# ProDoc_24_4_6__2025-08-03.net
KiCad netlist of a schematic drawn in EasyEDA Pro
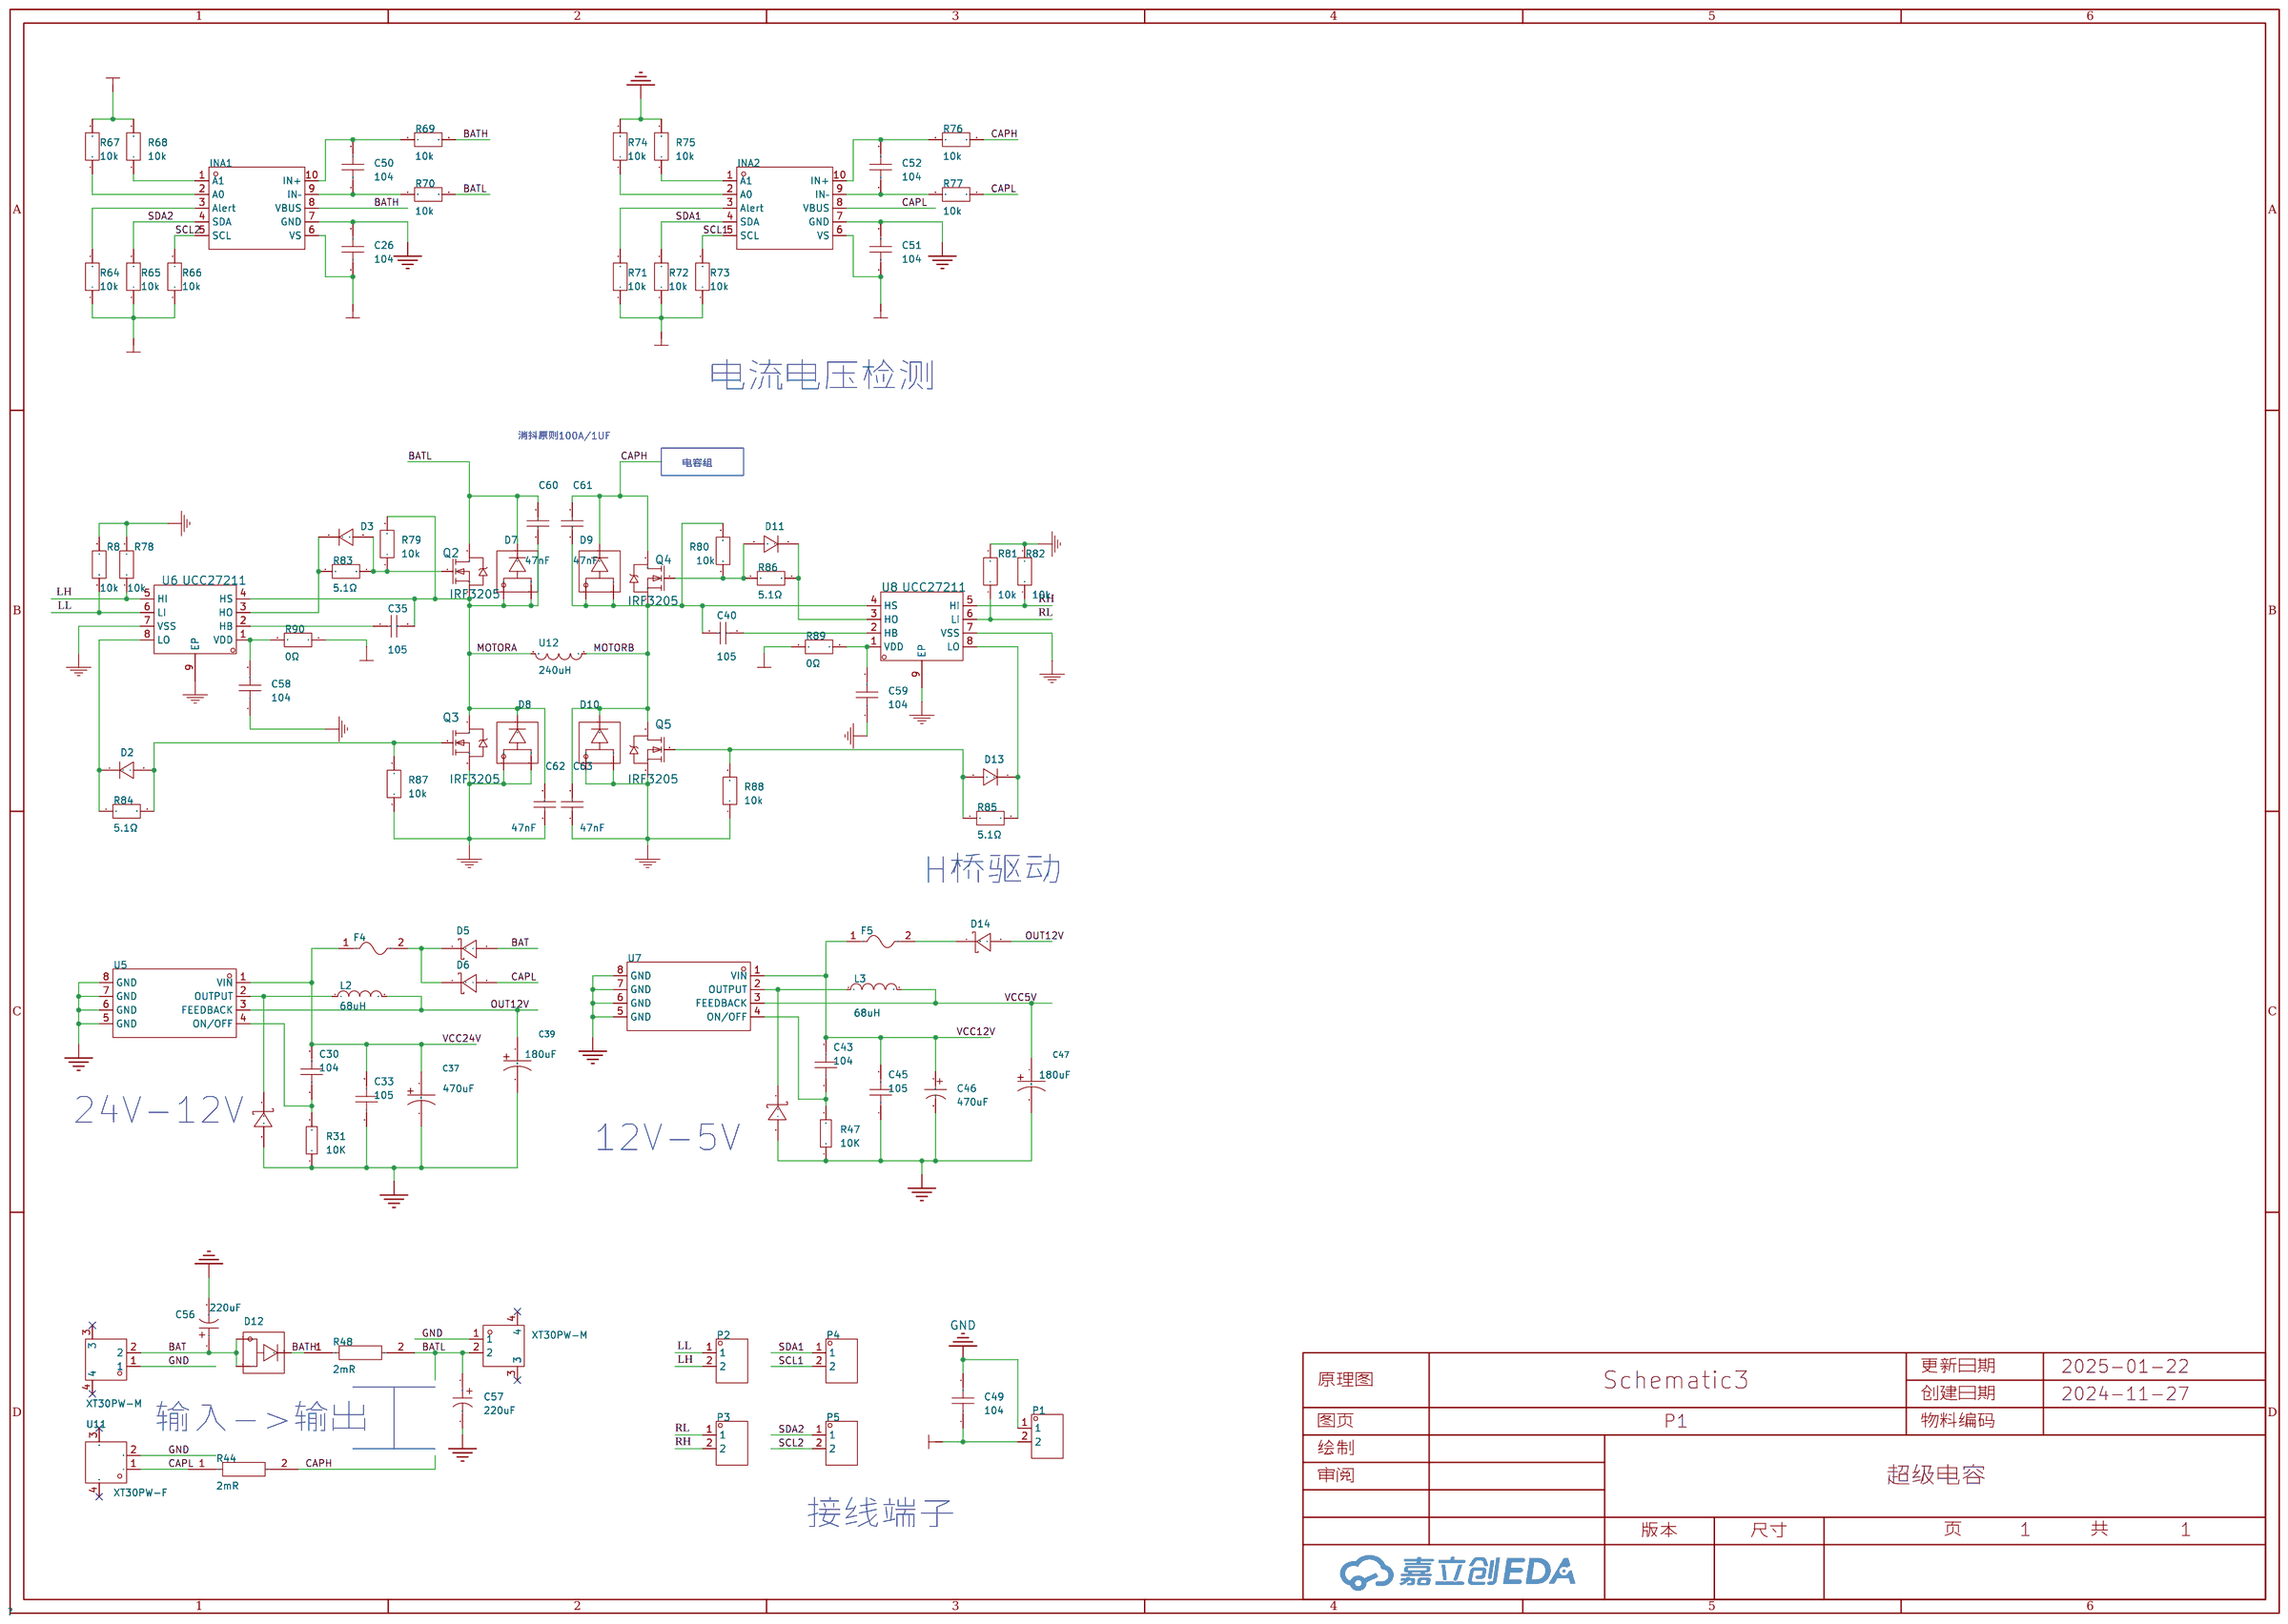
[diagram p0: schematic sheet]

(export (version "E")
  (design (tool "Eeschema 10.0.6"))
  (components
    (comp (ref "C26")
      (value "104")
      (footprint "easyedapro:C0603")
      (libsource (lib "easyedapro") (part "CapAcitance"))
    )
    (comp (ref "C30")
      (value "104")
      (footprint "easyedapro:C0603")
      (libsource (lib "easyedapro") (part "CapAcitance"))
    )
    (comp (ref "C33")
      (value "105")
      (footprint "easyedapro:C0603")
      (libsource (lib "easyedapro") (part "CapAcitance"))
    )
    (comp (ref "C35")
      (value "105")
      (footprint "easyedapro:C1206")
      (description "容值:10uF;精度:±10%;额定电压:50V;材质(温度系数):X5R;")
      (fields
        (field (name "Manufacturer Part") "CL31A106KBHNNNE")
        (field (name "Manufacturer") "SAMSUNG(三星)")
      )
      (libsource (lib "easyedapro") (part "CL31A106KBHNNNE"))
    )
    (comp (ref "C37")
      (value "470uF")
      (footprint "easyedapro:CAP-SMD_BD12.5-L13.0-W13.0-RD")
      (description "容值:470uF;精度:±20%;额定电压:50V;纹波电流:530mA@120Hz;等效串联电阻:-;")
      (fields (field (name "Manufacturer Part") "RVT1H471M1213") (field (name "Manufacturer") "ROQANG(容强)"))
      (libsource (lib "easyedapro") (part "RVT1H471M1213"))
    )
    (comp (ref "C39")
      (value "180uF")
      (footprint "easyedapro:CAP-SMD_BD8.0-L8.3-W8.3-FD")
      (fields (field (name "Manufacturer Part") "EEEFK1H181SP") (field (name "Manufacturer") "PANASONIC(松下)"))
      (libsource (lib "easyedapro") (part "EEEFK1H181SP"))
    )
    (comp (ref "C40")
      (value "105")
      (footprint "easyedapro:C1206")
      (description "容值:10uF;精度:±10%;额定电压:50V;材质(温度系数):X5R;")
      (fields
        (field (name "Manufacturer Part") "CL31A106KBHNNNE")
        (field (name "Manufacturer") "SAMSUNG(三星)")
      )
      (libsource (lib "easyedapro") (part "CL31A106KBHNNNE"))
    )
    (comp (ref "C43")
      (value "104")
      (footprint "easyedapro:C0603")
      (libsource (lib "easyedapro") (part "CapAcitance"))
    )
    (comp (ref "C45")
      (value "105")
      (footprint "easyedapro:C0603")
      (libsource (lib "easyedapro") (part "CapAcitance"))
    )
    (comp (ref "C46")
      (value "470uF")
      (footprint "easyedapro:CAP-SMD_BD10.0-L10.3-W10.3-FD")
      (description "容值:470uF;精度:±20%;额定电压:25V;纹波电流:286mA@120Hz;等效串联电阻:-;")
      (fields (field (name "Manufacturer Part") "RVT1E471M1010") (field (name "Manufacturer") "ROQANG(容强)"))
      (libsource (lib "easyedapro") (part "RVT1E471M1010"))
    )
    (comp (ref "C47")
      (value "180uF")
      (footprint "easyedapro:CAP-SMD_BD8.0-L8.3-W8.3-FD")
      (fields (field (name "Manufacturer Part") "EEEFK1H181SP") (field (name "Manufacturer") "PANASONIC(松下)"))
      (libsource (lib "easyedapro") (part "EEEFK1H181SP"))
    )
    (comp (ref "C49")
      (value "104")
      (footprint "easyedapro:C0603")
      (libsource (lib "easyedapro") (part "CapAcitance"))
    )
    (comp (ref "C50")
      (value "104")
      (footprint "easyedapro:C0603")
      (libsource (lib "easyedapro") (part "CapAcitance"))
    )
    (comp (ref "C51")
      (value "104")
      (footprint "easyedapro:C0603")
      (libsource (lib "easyedapro") (part "CapAcitance"))
    )
    (comp (ref "C52")
      (value "104")
      (footprint "easyedapro:C0603")
      (libsource (lib "easyedapro") (part "CapAcitance"))
    )
    (comp (ref "C56")
      (value "220uF")
      (footprint "easyedapro:CAP-SMD_BD6.3-L6.6-W6.6-FD")
      (description "容值:220uF;精度:±20%;额定电压:16V;纹波电流:110mA@120Hz;等效串联电阻:-;")
      (fields
        (field (name "Manufacturer Part") "RVT220UF16V67RV0015")
        (field (name "Manufacturer") "KNSCHA(科尼盛)")
      )
      (libsource (lib "easyedapro") (part "RVT220UF16V67RV0015"))
    )
    (comp (ref "C57")
      (value "220uF")
      (footprint "easyedapro:CAP-SMD_BD6.3-L6.6-W6.6-FD")
      (description "容值:220uF;精度:±20%;额定电压:16V;纹波电流:110mA@120Hz;等效串联电阻:-;")
      (fields
        (field (name "Manufacturer Part") "RVT220UF16V67RV0015")
        (field (name "Manufacturer") "KNSCHA(科尼盛)")
      )
      (libsource (lib "easyedapro") (part "RVT220UF16V67RV0015"))
    )
    (comp (ref "C58")
      (value "104")
      (footprint "easyedapro:C0603")
      (libsource (lib "easyedapro") (part "CapAcitance"))
    )
    (comp (ref "C59")
      (value "104")
      (footprint "easyedapro:C0603")
      (libsource (lib "easyedapro") (part "CapAcitance"))
    )
    (comp (ref "C60")
      (value "47nF")
      (footprint "easyedapro:C1206")
      (description "容值:10uF;精度:±10%;额定电压:50V;材质(温度系数):X5R;")
      (fields
        (field (name "Manufacturer Part") "CL31A106KBHNNNE")
        (field (name "Manufacturer") "SAMSUNG(三星)")
      )
      (libsource (lib "easyedapro") (part "CL31A106KBHNNNE"))
    )
    (comp (ref "C61")
      (value "47nF")
      (footprint "easyedapro:C1206")
      (description "容值:10uF;精度:±10%;额定电压:50V;材质(温度系数):X5R;")
      (fields
        (field (name "Manufacturer Part") "CL31A106KBHNNNE")
        (field (name "Manufacturer") "SAMSUNG(三星)")
      )
      (libsource (lib "easyedapro") (part "CL31A106KBHNNNE"))
    )
    (comp (ref "C62")
      (value "47nF")
      (footprint "easyedapro:C1206")
      (description "容值:10uF;精度:±10%;额定电压:50V;材质(温度系数):X5R;")
      (fields
        (field (name "Manufacturer Part") "CL31A106KBHNNNE")
        (field (name "Manufacturer") "SAMSUNG(三星)")
      )
      (libsource (lib "easyedapro") (part "CL31A106KBHNNNE"))
    )
    (comp (ref "C63")
      (value "47nF")
      (footprint "easyedapro:C1206")
      (description "容值:10uF;精度:±10%;额定电压:50V;材质(温度系数):X5R;")
      (fields
        (field (name "Manufacturer Part") "CL31A106KBHNNNE")
        (field (name "Manufacturer") "SAMSUNG(三星)")
      )
      (libsource (lib "easyedapro") (part "CL31A106KBHNNNE"))
    )
    (comp (ref "CN5")
      (value "XT30PW-M")
      (footprint "easyedapro:CONN-TH_XT30PW-M")
      (description "Socket,DCsupply,XT30,male,PIN:2")
      (fields (field (name "Manufacturer") "AMASS(艾迈斯)"))
      (libsource (lib "easyedapro") (part "XT30PW-M"))
    )
    (comp (ref "CN6")
      (value "XT30PW-M")
      (footprint "easyedapro:CONN-TH_XT30PW-M")
      (description "Socket,DCsupply,XT30,male,PIN:2")
      (fields (field (name "Manufacturer") "AMASS(艾迈斯)"))
      (libsource (lib "easyedapro") (part "XT30PW-M"))
    )
    (comp (ref "D2")
      (value "1N4148W")
      (footprint "easyedapro:SOD-123F_L2.7-W1.6-LS3.8-RD")
      (description "二极管配置:独立式;功率:400mW;直流反向耐压(Vr):75V;平均整流电流(Io):150mA;正向压降(Vf):1V@50mA;反向恢复时间(trr):4ns;")
      (fields (field (name "Manufacturer") "ST(先科)"))
      (libsource (lib "easyedapro") (part "1N4148W_C81598"))
    )
    (comp (ref "D3")
      (value "1N4148W")
      (footprint "easyedapro:SOD-123F_L2.7-W1.6-LS3.8-RD")
      (description "二极管配置:独立式;功率:400mW;直流反向耐压(Vr):75V;平均整流电流(Io):150mA;正向压降(Vf):1V@50mA;反向恢复时间(trr):4ns;")
      (fields (field (name "Manufacturer") "ST(先科)"))
      (libsource (lib "easyedapro") (part "1N4148W_C81598"))
    )
    (comp (ref "D5")
      (value "SS34K")
      (footprint "easyedapro:SMA_L4.3-W2.6-LS5.2-RD")
      (description "二极管配置:独立式;直流反向耐压(Vr):40V;平均整流电流(Io):3A;正向压降(Vf):550mV@3A;反向电流(Ir):500uA@40V;")
      (fields (field (name "Manufacturer") "TDD(台冠电子)"))
      (libsource (lib "easyedapro") (part "SS34K"))
    )
    (comp (ref "D6")
      (value "SS34K")
      (footprint "easyedapro:SMA_L4.3-W2.6-LS5.2-RD")
      (description "二极管配置:独立式;直流反向耐压(Vr):40V;平均整流电流(Io):3A;正向压降(Vf):550mV@3A;反向电流(Ir):500uA@40V;")
      (fields (field (name "Manufacturer") "TDD(台冠电子)"))
      (libsource (lib "easyedapro") (part "SS34K"))
    )
    (comp (ref "D7")
      (value "PSA2060LT")
      (footprint "easyedapro:PS-277A_L6.3-W4.7-LS7.1-RD")
      (description "直流反向耐压(Vr):60V;平均整流电流(Io):20A;正向压降(Vf):550mV@20A;")
      (fields (field (name "Manufacturer") "PINGWEI(平伟)"))
      (libsource (lib "easyedapro") (part "PSA2060LT"))
    )
    (comp (ref "D8")
      (value "PSA2060LT")
      (footprint "easyedapro:PS-277A_L6.3-W4.7-LS7.1-RD")
      (description "直流反向耐压(Vr):60V;平均整流电流(Io):20A;正向压降(Vf):550mV@20A;")
      (fields (field (name "Manufacturer") "PINGWEI(平伟)"))
      (libsource (lib "easyedapro") (part "PSA2060LT"))
    )
    (comp (ref "D9")
      (value "PSA2060LT")
      (footprint "easyedapro:PS-277A_L6.3-W4.7-LS7.1-RD")
      (description "直流反向耐压(Vr):60V;平均整流电流(Io):20A;正向压降(Vf):550mV@20A;")
      (fields (field (name "Manufacturer") "PINGWEI(平伟)"))
      (libsource (lib "easyedapro") (part "PSA2060LT"))
    )
    (comp (ref "D10")
      (value "PSA2060LT")
      (footprint "easyedapro:PS-277A_L6.3-W4.7-LS7.1-RD")
      (description "直流反向耐压(Vr):60V;平均整流电流(Io):20A;正向压降(Vf):550mV@20A;")
      (fields (field (name "Manufacturer") "PINGWEI(平伟)"))
      (libsource (lib "easyedapro") (part "PSA2060LT"))
    )
    (comp (ref "D11")
      (value "1N4148W")
      (footprint "easyedapro:SOD-123F_L2.7-W1.6-LS3.8-RD")
      (description "二极管配置:独立式;功率:400mW;直流反向耐压(Vr):75V;平均整流电流(Io):150mA;正向压降(Vf):1V@50mA;反向恢复时间(trr):4ns;")
      (fields (field (name "Manufacturer") "ST(先科)"))
      (libsource (lib "easyedapro") (part "1N4148W_C81598"))
    )
    (comp (ref "D12")
      (value "PSA2060LT")
      (footprint "easyedapro:PS-277A_L6.3-W4.7-LS7.1-RD")
      (description "直流反向耐压(Vr):60V;平均整流电流(Io):20A;正向压降(Vf):550mV@20A;")
      (fields (field (name "Manufacturer") "PINGWEI(平伟)"))
      (libsource (lib "easyedapro") (part "PSA2060LT"))
    )
    (comp (ref "D13")
      (value "1N4148W")
      (footprint "easyedapro:SOD-123F_L2.7-W1.6-LS3.8-RD")
      (description "二极管配置:独立式;功率:400mW;直流反向耐压(Vr):75V;平均整流电流(Io):150mA;正向压降(Vf):1V@50mA;反向恢复时间(trr):4ns;")
      (fields (field (name "Manufacturer") "ST(先科)"))
      (libsource (lib "easyedapro") (part "1N4148W_C81598"))
    )
    (comp (ref "D14")
      (value "SS34K")
      (footprint "easyedapro:SMA_L4.3-W2.6-LS5.2-RD")
      (description "二极管配置:独立式;直流反向耐压(Vr):40V;平均整流电流(Io):3A;正向压降(Vf):550mV@3A;反向电流(Ir):500uA@40V;")
      (fields (field (name "Manufacturer") "TDD(台冠电子)"))
      (libsource (lib "easyedapro") (part "SS34K"))
    )
    (comp (ref "F4")
      (value "nSMD020-30V")
      (footprint "easyedapro:F1206")
      (description "最大电压:30V;最大电流:100A;保持电流:200mA;跳闸电流:460mA;")
      (fields (field (name "Manufacturer") "台湾陆海"))
      (libsource (lib "easyedapro") (part "nSMD020-30V"))
    )
    (comp (ref "F5")
      (value "nSMD020-30V")
      (footprint "easyedapro:F1206")
      (description "最大电压:30V;最大电流:100A;保持电流:200mA;跳闸电流:460mA;")
      (fields (field (name "Manufacturer") "台湾陆海"))
      (libsource (lib "easyedapro") (part "nSMD020-30V"))
    )
    (comp (ref "INA1")
      (value "INA226AIDGST")
      (footprint "easyedapro:VSSOP-10_L3.0-W3.0-P0.50-LS4.9-BL")
      (fields (field (name "Manufacturer") "TI(德州仪器)"))
      (libsource (lib "easyedapro") (part "INA226AIDGST"))
    )
    (comp (ref "INA2")
      (value "INA226AIDGST")
      (footprint "easyedapro:VSSOP-10_L3.0-W3.0-P0.50-LS4.9-BL")
      (fields (field (name "Manufacturer") "TI(德州仪器)"))
      (libsource (lib "easyedapro") (part "INA226AIDGST"))
    )
    (comp (ref "L2")
      (value "68uH")
      (footprint "easyedapro:IND-SMD_L11.2-W10.0_GPSR1050")
      (description "类型:一体成型电感;电感值:68uH;精度:±20%;额定电流:-;饱和电流(Isat):-;")
      (fields (field (name "Manufacturer Part") "GPSR1050-680MS") (field (name "Manufacturer") "Gantong(感通)"))
      (libsource (lib "easyedapro") (part "GPSR1050-680MS"))
    )
    (comp (ref "L3")
      (value "68uH")
      (footprint "easyedapro:IND-SMD_L7.1-W6.6-1")
      (description "电感值:68uH;精度:±20%;额定电流:2A;饱和电流(Isat):2.5A;")
      (fields
        (field (name "Manufacturer Part") "PSPMAA0605H-680M-IGF")
        (field (name "Manufacturer") "PROD(谱罗德)")
      )
      (libsource (lib "easyedapro") (part "PSPMAA0605H-680M-IGF"))
    )
    (comp (ref "P1")
      (value "WJ15EDGRC-3.81-2P")
      (footprint "easyedapro:CONN-TH_2P-P3.81_WJ15EDGRC-3.81-2P")
      (description "连接器类型:板端/插座-闭口;间距:3.81mm;排数:1;每排PIN数:2;安装方式:弯针;颜色:绿色;")
      (fields (field (name "Manufacturer") "KANGNEX(康奈克斯电气)"))
      (libsource (lib "easyedapro") (part "WJ15EDGRC-3.81-2P"))
    )
    (comp (ref "P2")
      (value "WJ15EDGRC-3.81-2P")
      (footprint "easyedapro:CONN-TH_2P-P3.81_WJ15EDGRC-3.81-2P")
      (description "连接器类型:板端/插座-闭口;间距:3.81mm;排数:1;每排PIN数:2;安装方式:弯针;颜色:绿色;")
      (fields (field (name "Manufacturer") "KANGNEX(康奈克斯电气)"))
      (libsource (lib "easyedapro") (part "WJ15EDGRC-3.81-2P"))
    )
    (comp (ref "P3")
      (value "WJ15EDGRC-3.81-2P")
      (footprint "easyedapro:CONN-TH_2P-P3.81_WJ15EDGRC-3.81-2P")
      (description "连接器类型:板端/插座-闭口;间距:3.81mm;排数:1;每排PIN数:2;安装方式:弯针;颜色:绿色;")
      (fields (field (name "Manufacturer") "KANGNEX(康奈克斯电气)"))
      (libsource (lib "easyedapro") (part "WJ15EDGRC-3.81-2P"))
    )
    (comp (ref "P4")
      (value "WJ15EDGRC-3.81-2P")
      (footprint "easyedapro:CONN-TH_2P-P3.81_WJ15EDGRC-3.81-2P")
      (description "连接器类型:板端/插座-闭口;间距:3.81mm;排数:1;每排PIN数:2;安装方式:弯针;颜色:绿色;")
      (fields (field (name "Manufacturer") "KANGNEX(康奈克斯电气)"))
      (libsource (lib "easyedapro") (part "WJ15EDGRC-3.81-2P"))
    )
    (comp (ref "P5")
      (value "WJ15EDGRC-3.81-2P")
      (footprint "easyedapro:CONN-TH_2P-P3.81_WJ15EDGRC-3.81-2P")
      (description "连接器类型:板端/插座-闭口;间距:3.81mm;排数:1;每排PIN数:2;安装方式:弯针;颜色:绿色;")
      (fields (field (name "Manufacturer") "KANGNEX(康奈克斯电气)"))
      (libsource (lib "easyedapro") (part "WJ15EDGRC-3.81-2P"))
    )
    (comp (ref "Q2")
      (value "IRF3205")
      (footprint "easyedapro:TO-263-3_L10.2-W10.7-P5.08-LS16.2-BR")
      (fields
        (field (name "Manufacturer Part") "IRF3205ZSTRLPBF")
        (field (name "Manufacturer") "InfineonTechnologies")
      )
      (libsource (lib "easyedapro") (part "IRF3205ZSTRLPBF"))
    )
    (comp (ref "Q3")
      (value "IRF3205")
      (footprint "easyedapro:TO-263-3_L10.2-W10.7-P5.08-LS16.2-BR")
      (fields
        (field (name "Manufacturer Part") "IRF3205ZSTRLPBF")
        (field (name "Manufacturer") "InfineonTechnologies")
      )
      (libsource (lib "easyedapro") (part "IRF3205ZSTRLPBF"))
    )
    (comp (ref "Q4")
      (value "IRF3205")
      (footprint "easyedapro:TO-263-3_L10.2-W10.7-P5.08-LS16.2-BR")
      (fields
        (field (name "Manufacturer Part") "IRF3205ZSTRLPBF")
        (field (name "Manufacturer") "InfineonTechnologies")
      )
      (libsource (lib "easyedapro") (part "IRF3205ZSTRLPBF"))
    )
    (comp (ref "Q5")
      (value "IRF3205")
      (footprint "easyedapro:TO-263-3_L10.2-W10.7-P5.08-LS16.2-BR")
      (fields
        (field (name "Manufacturer Part") "IRF3205ZSTRLPBF")
        (field (name "Manufacturer") "InfineonTechnologies")
      )
      (libsource (lib "easyedapro") (part "IRF3205ZSTRLPBF"))
    )
    (comp (ref "R8")
      (value "10k")
      (footprint "easyedapro:R0603")
      (description "电阻类型:-;阻值:10kΩ;精度:±0.1%;功率:-;温度系数:±50ppm/;最大工作电压:50V;工作温度范围:-55~+125;")
      (fields (field (name "Manufacturer Part") "AR03BTD1002") (field (name "Manufacturer") "Viking(光颉)"))
      (libsource (lib "easyedapro") (part "AR03BTD1002"))
    )
    (comp (ref "R31") (value "10K") (footprint "easyedapro:R0603") (libsource (lib "easyedapro") (part "电阻")))
    (comp (ref "R44")
      (value "2mR")
      (footprint "easyedapro:RES-SMD_L6.4-W3.2-1")
      (description "电阻类型:采样电阻;阻值:30mΩ;精度:±1%;功率:2W;安装方式:贴片;")
      (fields
        (field (name "Manufacturer Part") "LCSR2512FR030Q9L")
        (field (name "Manufacturer") "RESI(开步睿思）")
      )
      (libsource (lib "easyedapro") (part "LCSR2512FR030Q9L"))
    )
    (comp (ref "R47") (value "10K") (footprint "easyedapro:R0603") (libsource (lib "easyedapro") (part "电阻")))
    (comp (ref "R48")
      (value "2mR")
      (footprint "easyedapro:RES-SMD_L6.4-W3.2-1")
      (description "电阻类型:采样电阻;阻值:30mΩ;精度:±1%;功率:2W;安装方式:贴片;")
      (fields
        (field (name "Manufacturer Part") "LCSR2512FR030Q9L")
        (field (name "Manufacturer") "RESI(开步睿思）")
      )
      (libsource (lib "easyedapro") (part "LCSR2512FR030Q9L"))
    )
    (comp (ref "R64")
      (value "10k")
      (footprint "easyedapro:R0603")
      (description "电阻类型:-;阻值:10kΩ;精度:±0.1%;功率:-;温度系数:±50ppm/;最大工作电压:50V;工作温度范围:-55~+125;")
      (fields (field (name "Manufacturer Part") "AR03BTD1002") (field (name "Manufacturer") "Viking(光颉)"))
      (libsource (lib "easyedapro") (part "AR03BTD1002"))
    )
    (comp (ref "R65")
      (value "10k")
      (footprint "easyedapro:R0603")
      (description "电阻类型:-;阻值:10kΩ;精度:±0.1%;功率:-;温度系数:±50ppm/;最大工作电压:50V;工作温度范围:-55~+125;")
      (fields (field (name "Manufacturer Part") "AR03BTD1002") (field (name "Manufacturer") "Viking(光颉)"))
      (libsource (lib "easyedapro") (part "AR03BTD1002"))
    )
    (comp (ref "R66")
      (value "10k")
      (footprint "easyedapro:R0603")
      (description "电阻类型:-;阻值:10kΩ;精度:±0.1%;功率:-;温度系数:±50ppm/;最大工作电压:50V;工作温度范围:-55~+125;")
      (fields (field (name "Manufacturer Part") "AR03BTD1002") (field (name "Manufacturer") "Viking(光颉)"))
      (libsource (lib "easyedapro") (part "AR03BTD1002"))
    )
    (comp (ref "R67")
      (value "10k")
      (footprint "easyedapro:R0603")
      (description "电阻类型:-;阻值:10kΩ;精度:±0.1%;功率:-;温度系数:±50ppm/;最大工作电压:50V;工作温度范围:-55~+125;")
      (fields (field (name "Manufacturer Part") "AR03BTD1002") (field (name "Manufacturer") "Viking(光颉)"))
      (libsource (lib "easyedapro") (part "AR03BTD1002"))
    )
    (comp (ref "R68")
      (value "10k")
      (footprint "easyedapro:R0603")
      (description "电阻类型:-;阻值:10kΩ;精度:±0.1%;功率:-;温度系数:±50ppm/;最大工作电压:50V;工作温度范围:-55~+125;")
      (fields (field (name "Manufacturer Part") "AR03BTD1002") (field (name "Manufacturer") "Viking(光颉)"))
      (libsource (lib "easyedapro") (part "AR03BTD1002"))
    )
    (comp (ref "R69")
      (value "10k")
      (footprint "easyedapro:R0603")
      (description "电阻类型:-;阻值:10kΩ;精度:±0.1%;功率:-;温度系数:±50ppm/;最大工作电压:50V;工作温度范围:-55~+125;")
      (fields (field (name "Manufacturer Part") "AR03BTD1002") (field (name "Manufacturer") "Viking(光颉)"))
      (libsource (lib "easyedapro") (part "AR03BTD1002"))
    )
    (comp (ref "R70")
      (value "10k")
      (footprint "easyedapro:R0603")
      (description "电阻类型:-;阻值:10kΩ;精度:±0.1%;功率:-;温度系数:±50ppm/;最大工作电压:50V;工作温度范围:-55~+125;")
      (fields (field (name "Manufacturer Part") "AR03BTD1002") (field (name "Manufacturer") "Viking(光颉)"))
      (libsource (lib "easyedapro") (part "AR03BTD1002"))
    )
    (comp (ref "R71")
      (value "10k")
      (footprint "easyedapro:R0603")
      (description "电阻类型:-;阻值:10kΩ;精度:±0.1%;功率:-;温度系数:±50ppm/;最大工作电压:50V;工作温度范围:-55~+125;")
      (fields (field (name "Manufacturer Part") "AR03BTD1002") (field (name "Manufacturer") "Viking(光颉)"))
      (libsource (lib "easyedapro") (part "AR03BTD1002"))
    )
    (comp (ref "R72")
      (value "10k")
      (footprint "easyedapro:R0603")
      (description "电阻类型:-;阻值:10kΩ;精度:±0.1%;功率:-;温度系数:±50ppm/;最大工作电压:50V;工作温度范围:-55~+125;")
      (fields (field (name "Manufacturer Part") "AR03BTD1002") (field (name "Manufacturer") "Viking(光颉)"))
      (libsource (lib "easyedapro") (part "AR03BTD1002"))
    )
    (comp (ref "R73")
      (value "10k")
      (footprint "easyedapro:R0603")
      (description "电阻类型:-;阻值:10kΩ;精度:±0.1%;功率:-;温度系数:±50ppm/;最大工作电压:50V;工作温度范围:-55~+125;")
      (fields (field (name "Manufacturer Part") "AR03BTD1002") (field (name "Manufacturer") "Viking(光颉)"))
      (libsource (lib "easyedapro") (part "AR03BTD1002"))
    )
    (comp (ref "R74")
      (value "10k")
      (footprint "easyedapro:R0603")
      (description "电阻类型:-;阻值:10kΩ;精度:±0.1%;功率:-;温度系数:±50ppm/;最大工作电压:50V;工作温度范围:-55~+125;")
      (fields (field (name "Manufacturer Part") "AR03BTD1002") (field (name "Manufacturer") "Viking(光颉)"))
      (libsource (lib "easyedapro") (part "AR03BTD1002"))
    )
    (comp (ref "R75")
      (value "10k")
      (footprint "easyedapro:R0603")
      (description "电阻类型:-;阻值:10kΩ;精度:±0.1%;功率:-;温度系数:±50ppm/;最大工作电压:50V;工作温度范围:-55~+125;")
      (fields (field (name "Manufacturer Part") "AR03BTD1002") (field (name "Manufacturer") "Viking(光颉)"))
      (libsource (lib "easyedapro") (part "AR03BTD1002"))
    )
    (comp (ref "R76")
      (value "10k")
      (footprint "easyedapro:R0603")
      (description "电阻类型:-;阻值:10kΩ;精度:±0.1%;功率:-;温度系数:±50ppm/;最大工作电压:50V;工作温度范围:-55~+125;")
      (fields (field (name "Manufacturer Part") "AR03BTD1002") (field (name "Manufacturer") "Viking(光颉)"))
      (libsource (lib "easyedapro") (part "AR03BTD1002"))
    )
    (comp (ref "R77")
      (value "10k")
      (footprint "easyedapro:R0603")
      (description "电阻类型:-;阻值:10kΩ;精度:±0.1%;功率:-;温度系数:±50ppm/;最大工作电压:50V;工作温度范围:-55~+125;")
      (fields (field (name "Manufacturer Part") "AR03BTD1002") (field (name "Manufacturer") "Viking(光颉)"))
      (libsource (lib "easyedapro") (part "AR03BTD1002"))
    )
    (comp (ref "R78")
      (value "10k")
      (footprint "easyedapro:R0603")
      (description "电阻类型:-;阻值:10kΩ;精度:±0.1%;功率:-;温度系数:±50ppm/;最大工作电压:50V;工作温度范围:-55~+125;")
      (fields (field (name "Manufacturer Part") "AR03BTD1002") (field (name "Manufacturer") "Viking(光颉)"))
      (libsource (lib "easyedapro") (part "AR03BTD1002"))
    )
    (comp (ref "R79")
      (value "10k")
      (footprint "easyedapro:R0603")
      (description "电阻类型:-;阻值:10kΩ;精度:±0.1%;功率:-;温度系数:±50ppm/;最大工作电压:50V;工作温度范围:-55~+125;")
      (fields (field (name "Manufacturer Part") "AR03BTD1002") (field (name "Manufacturer") "Viking(光颉)"))
      (libsource (lib "easyedapro") (part "AR03BTD1002"))
    )
    (comp (ref "R80")
      (value "10k")
      (footprint "easyedapro:R0603")
      (description "电阻类型:-;阻值:10kΩ;精度:±0.1%;功率:-;温度系数:±50ppm/;最大工作电压:50V;工作温度范围:-55~+125;")
      (fields (field (name "Manufacturer Part") "AR03BTD1002") (field (name "Manufacturer") "Viking(光颉)"))
      (libsource (lib "easyedapro") (part "AR03BTD1002"))
    )
    (comp (ref "R81")
      (value "10k")
      (footprint "easyedapro:R0603")
      (description "电阻类型:-;阻值:10kΩ;精度:±0.1%;功率:-;温度系数:±50ppm/;最大工作电压:50V;工作温度范围:-55~+125;")
      (fields (field (name "Manufacturer Part") "AR03BTD1002") (field (name "Manufacturer") "Viking(光颉)"))
      (libsource (lib "easyedapro") (part "AR03BTD1002"))
    )
    (comp (ref "R82")
      (value "10k")
      (footprint "easyedapro:R0603")
      (description "电阻类型:-;阻值:10kΩ;精度:±0.1%;功率:-;温度系数:±50ppm/;最大工作电压:50V;工作温度范围:-55~+125;")
      (fields (field (name "Manufacturer Part") "AR03BTD1002") (field (name "Manufacturer") "Viking(光颉)"))
      (libsource (lib "easyedapro") (part "AR03BTD1002"))
    )
    (comp (ref "R83")
      (value "5.1Ω")
      (footprint "easyedapro:R0603")
      (description "电阻类型:-;阻值:10kΩ;精度:±0.1%;功率:-;温度系数:±50ppm/;最大工作电压:50V;工作温度范围:-55~+125;")
      (fields (field (name "Manufacturer Part") "AR03BTD1002") (field (name "Manufacturer") "Viking(光颉)"))
      (libsource (lib "easyedapro") (part "AR03BTD1002"))
    )
    (comp (ref "R84")
      (value "5.1Ω")
      (footprint "easyedapro:R0603")
      (description "电阻类型:-;阻值:10kΩ;精度:±0.1%;功率:-;温度系数:±50ppm/;最大工作电压:50V;工作温度范围:-55~+125;")
      (fields (field (name "Manufacturer Part") "AR03BTD1002") (field (name "Manufacturer") "Viking(光颉)"))
      (libsource (lib "easyedapro") (part "AR03BTD1002"))
    )
    (comp (ref "R85")
      (value "5.1Ω")
      (footprint "easyedapro:R0603")
      (description "电阻类型:-;阻值:10kΩ;精度:±0.1%;功率:-;温度系数:±50ppm/;最大工作电压:50V;工作温度范围:-55~+125;")
      (fields (field (name "Manufacturer Part") "AR03BTD1002") (field (name "Manufacturer") "Viking(光颉)"))
      (libsource (lib "easyedapro") (part "AR03BTD1002"))
    )
    (comp (ref "R86")
      (value "5.1Ω")
      (footprint "easyedapro:R0603")
      (description "电阻类型:-;阻值:10kΩ;精度:±0.1%;功率:-;温度系数:±50ppm/;最大工作电压:50V;工作温度范围:-55~+125;")
      (fields (field (name "Manufacturer Part") "AR03BTD1002") (field (name "Manufacturer") "Viking(光颉)"))
      (libsource (lib "easyedapro") (part "AR03BTD1002"))
    )
    (comp (ref "R87")
      (value "10k")
      (footprint "easyedapro:R0603")
      (description "电阻类型:-;阻值:10kΩ;精度:±0.1%;功率:-;温度系数:±50ppm/;最大工作电压:50V;工作温度范围:-55~+125;")
      (fields (field (name "Manufacturer Part") "AR03BTD1002") (field (name "Manufacturer") "Viking(光颉)"))
      (libsource (lib "easyedapro") (part "AR03BTD1002"))
    )
    (comp (ref "R88")
      (value "10k")
      (footprint "easyedapro:R0603")
      (description "电阻类型:-;阻值:10kΩ;精度:±0.1%;功率:-;温度系数:±50ppm/;最大工作电压:50V;工作温度范围:-55~+125;")
      (fields (field (name "Manufacturer Part") "AR03BTD1002") (field (name "Manufacturer") "Viking(光颉)"))
      (libsource (lib "easyedapro") (part "AR03BTD1002"))
    )
    (comp (ref "R89")
      (value "0Ω")
      (footprint "easyedapro:R0603")
      (description "电阻类型:-;阻值:10kΩ;精度:±0.1%;功率:-;温度系数:±50ppm/;最大工作电压:50V;工作温度范围:-55~+125;")
      (fields (field (name "Manufacturer Part") "AR03BTD1002") (field (name "Manufacturer") "Viking(光颉)"))
      (libsource (lib "easyedapro") (part "AR03BTD1002"))
    )
    (comp (ref "R90")
      (value "0Ω")
      (footprint "easyedapro:R0603")
      (description "电阻类型:-;阻值:10kΩ;精度:±0.1%;功率:-;温度系数:±50ppm/;最大工作电压:50V;工作温度范围:-55~+125;")
      (fields (field (name "Manufacturer Part") "AR03BTD1002") (field (name "Manufacturer") "Viking(光颉)"))
      (libsource (lib "easyedapro") (part "AR03BTD1002"))
    )
    (comp (ref "SS2")
      (value "SS34K")
      (footprint "easyedapro:SMA_L4.3-W2.6-LS5.2-RD")
      (description "二极管配置:独立式;直流反向耐压(Vr):40V;平均整流电流(Io):3A;正向压降(Vf):550mV@3A;反向电流(Ir):500uA@40V;")
      (fields (field (name "Manufacturer") "TDD(台冠电子)"))
      (libsource (lib "easyedapro") (part "SS34K"))
    )
    (comp (ref "SS3")
      (value "SS34K")
      (footprint "easyedapro:SMA_L4.3-W2.6-LS5.2-RD")
      (description "二极管配置:独立式;直流反向耐压(Vr):40V;平均整流电流(Io):3A;正向压降(Vf):550mV@3A;反向电流(Ir):500uA@40V;")
      (fields (field (name "Manufacturer") "TDD(台冠电子)"))
      (libsource (lib "easyedapro") (part "SS34K"))
    )
    (comp (ref "U5")
      (value "XL1509-12")
      (footprint "easyedapro:SOIC-8_L4.9-W3.9-P1.27-LS6.0-BL")
      (fields (field (name "Manufacturer") "UMW(广东友台半导体)"))
      (libsource (lib "easyedapro") (part "XL1509-12"))
    )
    (comp (ref "U6")
      (value "UCC27211")
      (footprint "easyedapro:SOIC-8_L4.9-W3.9-P1.27-LS6.0-BL-EP")
      (fields
        (field (name "Manufacturer Part") "UCC27211DDAR")
        (field (name "Manufacturer") "TexasInstruments")
      )
      (libsource (lib "easyedapro") (part "UCC27211"))
    )
    (comp (ref "U7")
      (value "XL1509-12")
      (footprint "easyedapro:SOIC-8_L4.9-W3.9-P1.27-LS6.0-BL")
      (fields (field (name "Manufacturer") "UMW(广东友台半导体)"))
      (libsource (lib "easyedapro") (part "XL1509-12"))
    )
    (comp (ref "U8")
      (value "UCC27211")
      (footprint "easyedapro:SOIC-8_L4.9-W3.9-P1.27-LS6.0-BL-EP")
      (fields
        (field (name "Manufacturer Part") "UCC27211DDAR")
        (field (name "Manufacturer") "TexasInstruments")
      )
      (libsource (lib "easyedapro") (part "UCC27211"))
    )
    (comp (ref "U11")
      (value "XT30PW-F")
      (footprint "easyedapro:CONN-TH_XT30PW-F")
      (description "类别:-;类型1:-;")
      (fields (field (name "Manufacturer") "AMASS(艾迈斯)"))
      (libsource (lib "easyedapro") (part "XT30PW-F"))
    )
    (comp (ref "U12")
      (value "240uH")
      (footprint "easyedapro:IND-TH_L10.0-W6.0-P6.00")
      (description "电感值:60uH;精度:±10%;额定电流:-;饱和电流(Isat):-;类型:-;Q值:-;")
      (fields (field (name "Manufacturer Part") "DDGH00000050") (field (name "Manufacturer") "增益"))
      (libsource (lib "easyedapro") (part "DDGH00000050"))
    )
  )
  (nets
    (net (code "1") (name "/BAT") (class "Default")
      (node (ref "C56") (pin "1") (pinfunction "1_1") (pintype "input"))
      (node (ref "CN5") (pin "2") (pinfunction "2_2") (pintype "input"))
      (node (ref "D12") (pin "1") (pinfunction "1_1") (pintype "input"))
      (node (ref "D12") (pin "2") (pinfunction "2_2") (pintype "input"))
      (node (ref "D5") (pin "2") (pinfunction "A_2") (pintype "input"))
    )
    (net (code "2") (name "/BATH") (class "Default")
      (node (ref "D12") (pin "3") (pinfunction "3_3") (pintype "input"))
      (node (ref "INA1") (pin "8") (pinfunction "VBUS_8") (pintype "input"))
      (node (ref "R48") (pin "1") (pinfunction "1_1") (pintype "input"))
      (node (ref "R69") (pin "2") (pinfunction "2_2") (pintype "input"))
    )
    (net (code "3") (name "/BATL") (class "Default")
      (node (ref "C57") (pin "1") (pinfunction "1_1") (pintype "input"))
      (node (ref "C60") (pin "2") (pinfunction "2_2") (pintype "input"))
      (node (ref "CN6") (pin "2") (pinfunction "2_2") (pintype "input"))
      (node (ref "D7") (pin "3") (pinfunction "3_3") (pintype "input"))
      (node (ref "Q2") (pin "2") (pinfunction "D_2") (pintype "input"))
      (node (ref "R48") (pin "2") (pinfunction "2_2") (pintype "input"))
      (node (ref "R70") (pin "1") (pinfunction "1_1") (pintype "input"))
    )
    (net (code "4") (name "/CAPH") (class "Default")
      (node (ref "C61") (pin "2") (pinfunction "2_2") (pintype "input"))
      (node (ref "D9") (pin "3") (pinfunction "3_3") (pintype "input"))
      (node (ref "Q4") (pin "2") (pinfunction "D_2") (pintype "input"))
      (node (ref "R44") (pin "2") (pinfunction "2_2") (pintype "input"))
      (node (ref "R76") (pin "1") (pinfunction "1_1") (pintype "input"))
    )
    (net (code "5") (name "/CAPL") (class "Default")
      (node (ref "D6") (pin "2") (pinfunction "A_2") (pintype "input"))
      (node (ref "INA2") (pin "8") (pinfunction "VBUS_8") (pintype "input"))
      (node (ref "R44") (pin "1") (pinfunction "1_1") (pintype "input"))
      (node (ref "R77") (pin "1") (pinfunction "1_1") (pintype "input"))
      (node (ref "U11") (pin "1") (pinfunction "1_1") (pintype "unspecified"))
    )
    (net (code "6") (name "/LH") (class "Default")
      (node (ref "P2") (pin "2") (pinfunction "2_2") (pintype "input"))
      (node (ref "R78") (pin "1") (pinfunction "1_1") (pintype "input"))
      (node (ref "U6") (pin "5") (pinfunction "HI_5") (pintype "input"))
    )
    (net (code "7") (name "/LL") (class "Default")
      (node (ref "P2") (pin "1") (pinfunction "1_1") (pintype "input"))
      (node (ref "R8") (pin "1") (pinfunction "1_1") (pintype "input"))
      (node (ref "U6") (pin "6") (pinfunction "LI_6") (pintype "input"))
    )
    (net (code "8") (name "/MOTORA") (class "Default")
      (node (ref "C35") (pin "2") (pinfunction "2_2") (pintype "input"))
      (node (ref "C60") (pin "1") (pinfunction "1_1") (pintype "input"))
      (node (ref "C62") (pin "2") (pinfunction "2_2") (pintype "input"))
      (node (ref "D7") (pin "1") (pinfunction "1_1") (pintype "input"))
      (node (ref "D7") (pin "2") (pinfunction "2_2") (pintype "input"))
      (node (ref "D8") (pin "3") (pinfunction "3_3") (pintype "input"))
      (node (ref "Q2") (pin "3") (pinfunction "S_3") (pintype "input"))
      (node (ref "Q3") (pin "2") (pinfunction "D_2") (pintype "input"))
      (node (ref "R79") (pin "2") (pinfunction "2_2") (pintype "input"))
      (node (ref "U12") (pin "2") (pinfunction "2_2") (pintype "unspecified"))
      (node (ref "U6") (pin "4") (pinfunction "HS_4") (pintype "input"))
    )
    (net (code "9") (name "/MOTORB") (class "Default")
      (node (ref "C40") (pin "1") (pinfunction "1_1") (pintype "input"))
      (node (ref "C61") (pin "1") (pinfunction "1_1") (pintype "input"))
      (node (ref "C63") (pin "2") (pinfunction "2_2") (pintype "input"))
      (node (ref "D10") (pin "3") (pinfunction "3_3") (pintype "input"))
      (node (ref "D9") (pin "1") (pinfunction "1_1") (pintype "input"))
      (node (ref "D9") (pin "2") (pinfunction "2_2") (pintype "input"))
      (node (ref "Q4") (pin "3") (pinfunction "S_3") (pintype "input"))
      (node (ref "Q5") (pin "2") (pinfunction "D_2") (pintype "input"))
      (node (ref "R80") (pin "2") (pinfunction "2_2") (pintype "input"))
      (node (ref "U12") (pin "1") (pinfunction "1_1") (pintype "unspecified"))
      (node (ref "U8") (pin "4") (pinfunction "HS_4") (pintype "input"))
    )
    (net (code "10") (name "/OUT12V") (class "Default")
      (node (ref "C39") (pin "1") (pinfunction "1_1") (pintype "input"))
      (node (ref "D14") (pin "2") (pinfunction "A_2") (pintype "input"))
      (node (ref "L2") (pin "2") (pinfunction "2_2") (pintype "input"))
      (node (ref "U5") (pin "3") (pinfunction "FEEDBACK_3") (pintype "input"))
    )
    (net (code "11") (name "/RH") (class "Default")
      (node (ref "P3") (pin "2") (pinfunction "2_2") (pintype "input"))
      (node (ref "R82") (pin "1") (pinfunction "1_1") (pintype "input"))
      (node (ref "U8") (pin "5") (pinfunction "HI_5") (pintype "input"))
    )
    (net (code "12") (name "/RL") (class "Default")
      (node (ref "P3") (pin "1") (pinfunction "1_1") (pintype "input"))
      (node (ref "R81") (pin "1") (pinfunction "1_1") (pintype "input"))
      (node (ref "U8") (pin "6") (pinfunction "LI_6") (pintype "input"))
    )
    (net (code "13") (name "/SCL1") (class "Default")
      (node (ref "INA2") (pin "5") (pinfunction "SCL_5") (pintype "input"))
      (node (ref "P4") (pin "2") (pinfunction "2_2") (pintype "input"))
      (node (ref "R73") (pin "2") (pinfunction "2_2") (pintype "input"))
    )
    (net (code "14") (name "/SCL2") (class "Default")
      (node (ref "INA1") (pin "5") (pinfunction "SCL_5") (pintype "input"))
      (node (ref "P5") (pin "2") (pinfunction "2_2") (pintype "input"))
      (node (ref "R66") (pin "2") (pinfunction "2_2") (pintype "input"))
    )
    (net (code "15") (name "/SDA1") (class "Default")
      (node (ref "INA2") (pin "4") (pinfunction "SDA_4") (pintype "input"))
      (node (ref "P4") (pin "1") (pinfunction "1_1") (pintype "input"))
      (node (ref "R72") (pin "2") (pinfunction "2_2") (pintype "input"))
    )
    (net (code "16") (name "/SDA2") (class "Default")
      (node (ref "INA1") (pin "4") (pinfunction "SDA_4") (pintype "input"))
      (node (ref "P5") (pin "1") (pinfunction "1_1") (pintype "input"))
      (node (ref "R65") (pin "2") (pinfunction "2_2") (pintype "input"))
    )
    (net (code "17") (name "/VCC24V") (class "Default")
      (node (ref "C30") (pin "2") (pinfunction "2_2") (pintype "input"))
      (node (ref "C33") (pin "2") (pinfunction "2_2") (pintype "input"))
      (node (ref "C37") (pin "1") (pinfunction "1_1") (pintype "input"))
      (node (ref "F4") (pin "1") (pinfunction "1_1") (pintype "unspecified"))
      (node (ref "U5") (pin "1") (pinfunction "VIN_1") (pintype "input"))
    )
    (net (code "18") (name "GND") (class "Default")
      (node (ref "C26") (pin "2") (pinfunction "2_2") (pintype "input"))
      (node (ref "C33") (pin "1") (pinfunction "1_1") (pintype "input"))
      (node (ref "C37") (pin "2") (pinfunction "2_2") (pintype "input"))
      (node (ref "C39") (pin "2") (pinfunction "2_2") (pintype "input"))
      (node (ref "C45") (pin "1") (pinfunction "1_1") (pintype "input"))
      (node (ref "C46") (pin "2") (pinfunction "2_2") (pintype "input"))
      (node (ref "C47") (pin "2") (pinfunction "2_2") (pintype "input"))
      (node (ref "C49") (pin "2") (pinfunction "2_2") (pintype "input"))
      (node (ref "C51") (pin "2") (pinfunction "2_2") (pintype "input"))
      (node (ref "C56") (pin "2") (pinfunction "2_2") (pintype "input"))
      (node (ref "C57") (pin "2") (pinfunction "2_2") (pintype "input"))
      (node (ref "C58") (pin "1") (pinfunction "1_1") (pintype "input"))
      (node (ref "C59") (pin "1") (pinfunction "1_1") (pintype "input"))
      (node (ref "C62") (pin "1") (pinfunction "1_1") (pintype "input"))
      (node (ref "C63") (pin "1") (pinfunction "1_1") (pintype "input"))
      (node (ref "CN5") (pin "1") (pinfunction "1_1") (pintype "input"))
      (node (ref "CN6") (pin "1") (pinfunction "1_1") (pintype "input"))
      (node (ref "D10") (pin "1") (pinfunction "1_1") (pintype "input"))
      (node (ref "D10") (pin "2") (pinfunction "2_2") (pintype "input"))
      (node (ref "D8") (pin "1") (pinfunction "1_1") (pintype "input"))
      (node (ref "D8") (pin "2") (pinfunction "2_2") (pintype "input"))
      (node (ref "INA1") (pin "7") (pinfunction "GND_7") (pintype "input"))
      (node (ref "INA2") (pin "7") (pinfunction "GND_7") (pintype "input"))
      (node (ref "P1") (pin "1") (pinfunction "1_1") (pintype "input"))
      (node (ref "Q3") (pin "3") (pinfunction "S_3") (pintype "input"))
      (node (ref "Q5") (pin "3") (pinfunction "S_3") (pintype "input"))
      (node (ref "R31") (pin "1") (pinfunction "1_1") (pintype "input"))
      (node (ref "R47") (pin "1") (pinfunction "1_1") (pintype "input"))
      (node (ref "R74") (pin "2") (pinfunction "2_2") (pintype "input"))
      (node (ref "R75") (pin "2") (pinfunction "2_2") (pintype "input"))
      (node (ref "R78") (pin "2") (pinfunction "2_2") (pintype "input"))
      (node (ref "R8") (pin "2") (pinfunction "2_2") (pintype "input"))
      (node (ref "R81") (pin "2") (pinfunction "2_2") (pintype "input"))
      (node (ref "R82") (pin "2") (pinfunction "2_2") (pintype "input"))
      (node (ref "R87") (pin "1") (pinfunction "1_1") (pintype "input"))
      (node (ref "R88") (pin "1") (pinfunction "1_1") (pintype "input"))
      (node (ref "SS2") (pin "2") (pinfunction "A_2") (pintype "input"))
      (node (ref "SS3") (pin "2") (pinfunction "A_2") (pintype "input"))
      (node (ref "U11") (pin "2") (pinfunction "2_2") (pintype "unspecified"))
      (node (ref "U5") (pin "5") (pinfunction "GND_5") (pintype "input"))
      (node (ref "U5") (pin "6") (pinfunction "GND_6") (pintype "input"))
      (node (ref "U5") (pin "7") (pinfunction "GND_7") (pintype "input"))
      (node (ref "U5") (pin "8") (pinfunction "GND_8") (pintype "input"))
      (node (ref "U6") (pin "7") (pinfunction "VSS_7") (pintype "input"))
      (node (ref "U6") (pin "9") (pinfunction "EP_9") (pintype "input"))
      (node (ref "U7") (pin "5") (pinfunction "GND_5") (pintype "input"))
      (node (ref "U7") (pin "6") (pinfunction "GND_6") (pintype "input"))
      (node (ref "U7") (pin "7") (pinfunction "GND_7") (pintype "input"))
      (node (ref "U7") (pin "8") (pinfunction "GND_8") (pintype "input"))
      (node (ref "U8") (pin "7") (pinfunction "VSS_7") (pintype "input"))
      (node (ref "U8") (pin "9") (pinfunction "EP_9") (pintype "input"))
    )
    (net (code "19") (name "Net-(D2-A)") (class "Default")
      (node (ref "D2") (pin "2") (pinfunction "A_2") (pintype "input"))
      (node (ref "Q3") (pin "1") (pinfunction "G_1") (pintype "input"))
      (node (ref "R84") (pin "2") (pinfunction "2_2") (pintype "input"))
      (node (ref "R87") (pin "2") (pinfunction "2_2") (pintype "input"))
    )
    (net (code "20") (name "Net-(D2-K)") (class "Default")
      (node (ref "D2") (pin "1") (pinfunction "K_1") (pintype "input"))
      (node (ref "R84") (pin "1") (pinfunction "1_1") (pintype "input"))
      (node (ref "U6") (pin "8") (pinfunction "LO_8") (pintype "input"))
    )
    (net (code "21") (name "Net-(D3-A)") (class "Default")
      (node (ref "D3") (pin "2") (pinfunction "A_2") (pintype "input"))
      (node (ref "Q2") (pin "1") (pinfunction "G_1") (pintype "input"))
      (node (ref "R79") (pin "1") (pinfunction "1_1") (pintype "input"))
      (node (ref "R83") (pin "2") (pinfunction "2_2") (pintype "input"))
    )
    (net (code "22") (name "Net-(D3-K)") (class "Default")
      (node (ref "D3") (pin "1") (pinfunction "K_1") (pintype "input"))
      (node (ref "R83") (pin "1") (pinfunction "1_1") (pintype "input"))
      (node (ref "U6") (pin "3") (pinfunction "HO_3") (pintype "input"))
    )
    (net (code "23") (name "Net-(D5-C)") (class "Default")
      (node (ref "D5") (pin "1") (pinfunction "C_1") (pintype "input"))
      (node (ref "D6") (pin "1") (pinfunction "C_1") (pintype "input"))
      (node (ref "F4") (pin "2") (pinfunction "2_2") (pintype "unspecified"))
    )
    (net (code "24") (name "Net-(D11-A)") (class "Default")
      (node (ref "D11") (pin "2") (pinfunction "A_2") (pintype "input"))
      (node (ref "Q4") (pin "1") (pinfunction "G_1") (pintype "input"))
      (node (ref "R80") (pin "1") (pinfunction "1_1") (pintype "input"))
      (node (ref "R86") (pin "1") (pinfunction "1_1") (pintype "input"))
    )
    (net (code "25") (name "Net-(D11-K)") (class "Default")
      (node (ref "D11") (pin "1") (pinfunction "K_1") (pintype "input"))
      (node (ref "R86") (pin "2") (pinfunction "2_2") (pintype "input"))
      (node (ref "U8") (pin "3") (pinfunction "HO_3") (pintype "input"))
    )
    (net (code "26") (name "Net-(D13-A)") (class "Default")
      (node (ref "D13") (pin "2") (pinfunction "A_2") (pintype "input"))
      (node (ref "Q5") (pin "1") (pinfunction "G_1") (pintype "input"))
      (node (ref "R85") (pin "1") (pinfunction "1_1") (pintype "input"))
      (node (ref "R88") (pin "2") (pinfunction "2_2") (pintype "input"))
    )
    (net (code "27") (name "Net-(D13-K)") (class "Default")
      (node (ref "D13") (pin "1") (pinfunction "K_1") (pintype "input"))
      (node (ref "R85") (pin "2") (pinfunction "2_2") (pintype "input"))
      (node (ref "U8") (pin "8") (pinfunction "LO_8") (pintype "input"))
    )
    (net (code "28") (name "Net-(D14-C)") (class "Default")
      (node (ref "D14") (pin "1") (pinfunction "C_1") (pintype "input"))
      (node (ref "F5") (pin "2") (pinfunction "2_2") (pintype "unspecified"))
    )
    (net (code "29") (name "Net-(INA1-A0)") (class "Default")
      (node (ref "INA1") (pin "2") (pinfunction "A0_2") (pintype "input"))
      (node (ref "R67") (pin "1") (pinfunction "1_1") (pintype "input"))
    )
    (net (code "30") (name "Net-(INA1-A1)") (class "Default")
      (node (ref "INA1") (pin "1") (pinfunction "A1_1") (pintype "input"))
      (node (ref "R68") (pin "1") (pinfunction "1_1") (pintype "input"))
    )
    (net (code "31") (name "Net-(INA1-Alert)") (class "Default")
      (node (ref "INA1") (pin "3") (pinfunction "Alert_3") (pintype "input"))
      (node (ref "R64") (pin "2") (pinfunction "2_2") (pintype "input"))
    )
    (net (code "32") (name "Net-(INA1-IN+)") (class "Default")
      (node (ref "C50") (pin "2") (pinfunction "2_2") (pintype "input"))
      (node (ref "INA1") (pin "10") (pinfunction "IN+_10") (pintype "input"))
      (node (ref "R69") (pin "1") (pinfunction "1_1") (pintype "input"))
    )
    (net (code "33") (name "Net-(INA1-IN–)") (class "Default")
      (node (ref "C50") (pin "1") (pinfunction "1_1") (pintype "input"))
      (node (ref "INA1") (pin "9") (pinfunction "IN–_9") (pintype "input"))
      (node (ref "R70") (pin "2") (pinfunction "2_2") (pintype "input"))
    )
    (net (code "34") (name "Net-(INA2-A0)") (class "Default")
      (node (ref "INA2") (pin "2") (pinfunction "A0_2") (pintype "input"))
      (node (ref "R74") (pin "1") (pinfunction "1_1") (pintype "input"))
    )
    (net (code "35") (name "Net-(INA2-A1)") (class "Default")
      (node (ref "INA2") (pin "1") (pinfunction "A1_1") (pintype "input"))
      (node (ref "R75") (pin "1") (pinfunction "1_1") (pintype "input"))
    )
    (net (code "36") (name "Net-(INA2-Alert)") (class "Default")
      (node (ref "INA2") (pin "3") (pinfunction "Alert_3") (pintype "input"))
      (node (ref "R71") (pin "2") (pinfunction "2_2") (pintype "input"))
    )
    (net (code "37") (name "Net-(INA2-IN+)") (class "Default")
      (node (ref "C52") (pin "2") (pinfunction "2_2") (pintype "input"))
      (node (ref "INA2") (pin "10") (pinfunction "IN+_10") (pintype "input"))
      (node (ref "R76") (pin "2") (pinfunction "2_2") (pintype "input"))
    )
    (net (code "38") (name "Net-(INA2-IN–)") (class "Default")
      (node (ref "C52") (pin "1") (pinfunction "1_1") (pintype "input"))
      (node (ref "INA2") (pin "9") (pinfunction "IN–_9") (pintype "input"))
      (node (ref "R77") (pin "2") (pinfunction "2_2") (pintype "input"))
    )
    (net (code "39") (name "Net-(SS2-C)") (class "Default")
      (node (ref "L2") (pin "1") (pinfunction "1_1") (pintype "input"))
      (node (ref "SS2") (pin "1") (pinfunction "C_1") (pintype "input"))
      (node (ref "U5") (pin "2") (pinfunction "OUTPUT_2") (pintype "input"))
    )
    (net (code "40") (name "Net-(SS3-C)") (class "Default")
      (node (ref "L3") (pin "1") (pinfunction "1_1") (pintype "input"))
      (node (ref "SS3") (pin "1") (pinfunction "C_1") (pintype "input"))
      (node (ref "U7") (pin "2") (pinfunction "OUTPUT_2") (pintype "input"))
    )
    (net (code "41") (name "Net-(U5-ON{slash}OFF)") (class "Default")
      (node (ref "C30") (pin "1") (pinfunction "1_1") (pintype "input"))
      (node (ref "R31") (pin "2") (pinfunction "2_2") (pintype "input"))
      (node (ref "U5") (pin "4") (pinfunction "ON/OFF_4") (pintype "input"))
    )
    (net (code "42") (name "Net-(U6-HB)") (class "Default")
      (node (ref "C35") (pin "1") (pinfunction "1_1") (pintype "input"))
      (node (ref "U6") (pin "2") (pinfunction "HB_2") (pintype "input"))
    )
    (net (code "43") (name "Net-(U6-VDD)") (class "Default")
      (node (ref "C58") (pin "2") (pinfunction "2_2") (pintype "input"))
      (node (ref "R90") (pin "2") (pinfunction "2_2") (pintype "input"))
      (node (ref "U6") (pin "1") (pinfunction "VDD_1") (pintype "input"))
    )
    (net (code "44") (name "Net-(U7-ON{slash}OFF)") (class "Default")
      (node (ref "C43") (pin "1") (pinfunction "1_1") (pintype "input"))
      (node (ref "R47") (pin "2") (pinfunction "2_2") (pintype "input"))
      (node (ref "U7") (pin "4") (pinfunction "ON/OFF_4") (pintype "input"))
    )
    (net (code "45") (name "Net-(U8-HB)") (class "Default")
      (node (ref "C40") (pin "2") (pinfunction "2_2") (pintype "input"))
      (node (ref "U8") (pin "2") (pinfunction "HB_2") (pintype "input"))
    )
    (net (code "46") (name "Net-(U8-VDD)") (class "Default")
      (node (ref "C59") (pin "2") (pinfunction "2_2") (pintype "input"))
      (node (ref "R89") (pin "1") (pinfunction "1_1") (pintype "input"))
      (node (ref "U8") (pin "1") (pinfunction "VDD_1") (pintype "input"))
    )
    (net (code "47") (name "VCC5V") (class "Default")
      (node (ref "C26") (pin "1") (pinfunction "1_1") (pintype "input"))
      (node (ref "C47") (pin "1") (pinfunction "1_1") (pintype "input"))
      (node (ref "C49") (pin "1") (pinfunction "1_1") (pintype "input"))
      (node (ref "C51") (pin "1") (pinfunction "1_1") (pintype "input"))
      (node (ref "INA1") (pin "6") (pinfunction "VS_6") (pintype "input"))
      (node (ref "INA2") (pin "6") (pinfunction "VS_6") (pintype "input"))
      (node (ref "L3") (pin "2") (pinfunction "2_2") (pintype "input"))
      (node (ref "P1") (pin "2") (pinfunction "2_2") (pintype "input"))
      (node (ref "R67") (pin "2") (pinfunction "2_2") (pintype "input"))
      (node (ref "R68") (pin "2") (pinfunction "2_2") (pintype "input"))
      (node (ref "U7") (pin "3") (pinfunction "FEEDBACK_3") (pintype "input"))
    )
    (net (code "48") (name "VCC12V") (class "Default")
      (node (ref "C43") (pin "2") (pinfunction "2_2") (pintype "input"))
      (node (ref "C45") (pin "2") (pinfunction "2_2") (pintype "input"))
      (node (ref "C46") (pin "1") (pinfunction "1_1") (pintype "input"))
      (node (ref "F5") (pin "1") (pinfunction "1_1") (pintype "unspecified"))
      (node (ref "R64") (pin "1") (pinfunction "1_1") (pintype "input"))
      (node (ref "R65") (pin "1") (pinfunction "1_1") (pintype "input"))
      (node (ref "R66") (pin "1") (pinfunction "1_1") (pintype "input"))
      (node (ref "R71") (pin "1") (pinfunction "1_1") (pintype "input"))
      (node (ref "R72") (pin "1") (pinfunction "1_1") (pintype "input"))
      (node (ref "R73") (pin "1") (pinfunction "1_1") (pintype "input"))
      (node (ref "R89") (pin "2") (pinfunction "2_2") (pintype "input"))
      (node (ref "R90") (pin "1") (pinfunction "1_1") (pintype "input"))
      (node (ref "U7") (pin "1") (pinfunction "VIN_1") (pintype "input"))
    )
    (net (code "49") (name "unconnected-(CN5-Pad3)") (class "Default")
      (node (ref "CN5") (pin "3") (pinfunction "3_3") (pintype "input+no_connect"))
    )
    (net (code "50") (name "unconnected-(CN5-Pad4)") (class "Default")
      (node (ref "CN5") (pin "4") (pinfunction "4_4") (pintype "input+no_connect"))
    )
    (net (code "51") (name "unconnected-(CN6-Pad3)") (class "Default")
      (node (ref "CN6") (pin "3") (pinfunction "3_3") (pintype "input+no_connect"))
    )
    (net (code "52") (name "unconnected-(CN6-Pad4)") (class "Default")
      (node (ref "CN6") (pin "4") (pinfunction "4_4") (pintype "input+no_connect"))
    )
    (net (code "53") (name "unconnected-(U11-Pad3)") (class "Default")
      (node (ref "U11") (pin "3") (pinfunction "3_3") (pintype "unspecified+no_connect"))
    )
    (net (code "54") (name "unconnected-(U11-Pad4)") (class "Default")
      (node (ref "U11") (pin "4") (pinfunction "4_4") (pintype "unspecified+no_connect"))
    )
  )
)
